# Sheet1.net
KiCad netlist of a schematic drawn in Altium Designer
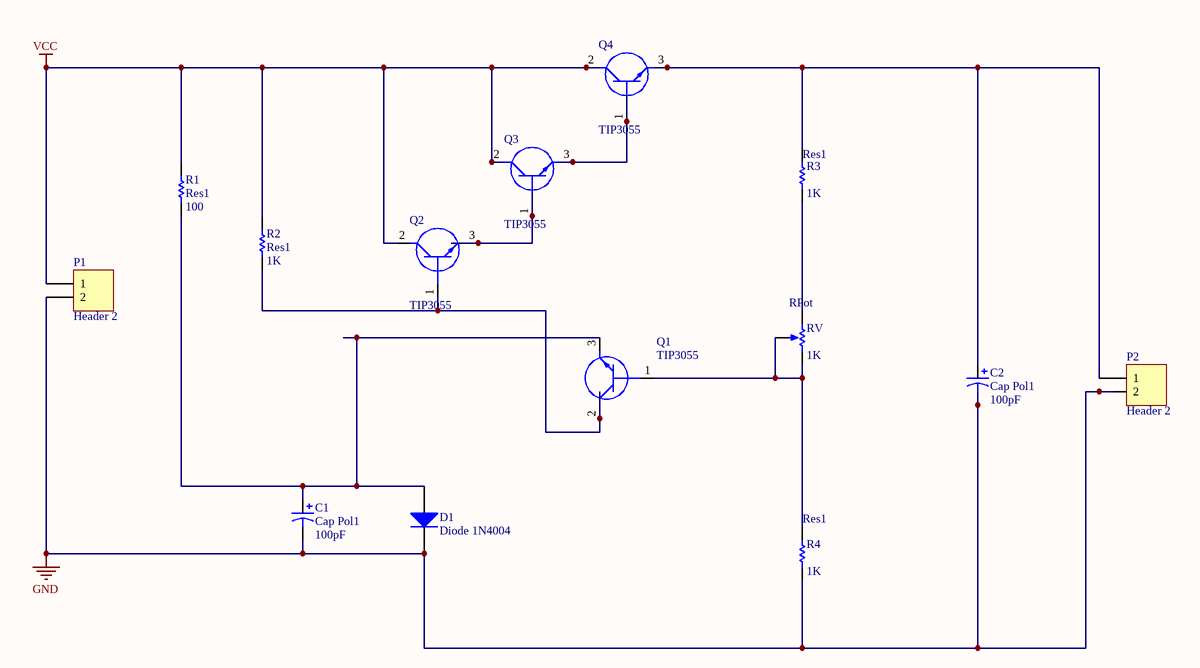
[diagram p0: Sheet1.SchDoc]

(export (version "E")
  (design (tool "Eeschema 10.0.6"))
  (components
    (comp (ref "C1")
      (value "Cap Pol1")
      (footprint "RB7.6-15")
      (description "Polarized Capacitor (Radial)")
      (fields (field (name "ALTIUM_VALUE") "100pF") (field (name "PUBLISHER") "Altium Limited"))
      (libsource (lib "Miscellaneous Devices") (part "Cap Pol1"))
    )
    (comp (ref "C2")
      (value "Cap Pol1")
      (footprint "RB7.6-15")
      (description "Polarized Capacitor (Radial)")
      (fields (field (name "ALTIUM_VALUE") "100pF") (field (name "PUBLISHER") "Altium Limited"))
      (libsource (lib "Miscellaneous Devices") (part "Cap Pol1"))
    )
    (comp (ref "D1")
      (value "Diode 1N4004")
      (footprint "DO-41")
      (description "1 Amp General Purpose Rectifier")
      (fields (field (name "PUBLISHER") "Altium Limited"))
      (libsource (lib "Miscellaneous Devices") (part "Diode 1N4004"))
    )
    (comp (ref "P1")
      (value "Header 2")
      (footprint "HDR1X2")
      (description "Header, 2-Pin")
      (fields (field (name "PUBLISHER") "Altium Limited"))
      (libsource (lib "Miscellaneous Connectors") (part "Header 2"))
    )
    (comp (ref "P2")
      (value "Header 2")
      (footprint "HDR1X2")
      (description "Header, 2-Pin")
      (fields (field (name "PUBLISHER") "Altium Limited"))
      (libsource (lib "Miscellaneous Connectors") (part "Header 2"))
    )
    (comp (ref "Q1")
      (value "TIP3055")
      (footprint "SamacSys:TO545P515X1560X2445-3P")
      (description "Transistor BJT NPN")
      (fields (field (name "MOUSER PART NUMBER") "511-TIP3055") (field (name "RS PART NUMBER") "1686168"))
      (libsource (lib "*") (part "TIP3055"))
    )
    (comp (ref "Q2")
      (value "TIP3055")
      (footprint "SamacSys:TO545P515X1560X2445-3P")
      (description "Transistor BJT NPN")
      (fields (field (name "MOUSER PART NUMBER") "511-TIP3055") (field (name "RS PART NUMBER") "1686168"))
      (libsource (lib "*") (part "TIP3055"))
    )
    (comp (ref "Q3")
      (value "TIP3055")
      (footprint "SamacSys:TO545P515X1560X2445-3P")
      (description "Transistor BJT NPN")
      (fields (field (name "MOUSER PART NUMBER") "511-TIP3055") (field (name "RS PART NUMBER") "1686168"))
      (libsource (lib "*") (part "TIP3055"))
    )
    (comp (ref "Q4")
      (value "TIP3055")
      (footprint "SamacSys:TO545P515X1560X2445-3P")
      (description "Transistor BJT NPN")
      (fields (field (name "MOUSER PART NUMBER") "511-TIP3055") (field (name "RS PART NUMBER") "1686168"))
      (libsource (lib "*") (part "TIP3055"))
    )
    (comp (ref "R1")
      (value "Res1")
      (footprint "AXIAL-0.3")
      (description "Resistor")
      (fields (field (name "ALTIUM_VALUE") "100") (field (name "PUBLISHER") "Altium Limited"))
      (libsource (lib "Miscellaneous Devices") (part "Res1"))
    )
    (comp (ref "R2")
      (value "Res1")
      (footprint "AXIAL-0.3")
      (description "Resistor")
      (fields (field (name "ALTIUM_VALUE") "1K") (field (name "PUBLISHER") "Altium Limited"))
      (libsource (lib "Miscellaneous Devices") (part "Res1"))
    )
    (comp (ref "R3")
      (value "Res1")
      (footprint "AXIAL-0.3")
      (description "Resistor")
      (fields (field (name "ALTIUM_VALUE") "1K") (field (name "PUBLISHER") "Altium Limited"))
      (libsource (lib "Miscellaneous Devices") (part "Res1"))
    )
    (comp (ref "R4")
      (value "Res1")
      (footprint "AXIAL-0.3")
      (description "Resistor")
      (fields (field (name "ALTIUM_VALUE") "1K") (field (name "PUBLISHER") "Altium Limited"))
      (libsource (lib "Miscellaneous Devices") (part "Res1"))
    )
    (comp (ref "RV")
      (value "RPot")
      (footprint "VR5")
      (description "Potentiometer")
      (fields (field (name "ALTIUM_VALUE") "1K") (field (name "PUBLISHER") "Altium Limited"))
      (libsource (lib "Miscellaneous Devices") (part "RPot"))
    )
  )
  (nets
    (net (code "1") (name "GND") (class "Default")
      (node (ref "C1") (pin "2") (pinfunction "2_2") (pintype "passive"))
      (node (ref "C2") (pin "2") (pinfunction "2_2") (pintype "passive"))
      (node (ref "D1") (pin "2") (pinfunction "K_2") (pintype "passive"))
      (node (ref "P1") (pin "2") (pinfunction "2_2") (pintype "passive"))
      (node (ref "P2") (pin "2") (pinfunction "2_2") (pintype "passive"))
      (node (ref "R4") (pin "1") (pinfunction "1_1") (pintype "passive"))
    )
    (net (code "2") (name "Net-(D1-A)") (class "Default")
      (node (ref "C1") (pin "1") (pinfunction "1_1") (pintype "passive"))
      (node (ref "D1") (pin "1") (pinfunction "A_1") (pintype "passive"))
      (node (ref "Q1") (pin "3") (pinfunction "E_3") (pintype "passive"))
      (node (ref "R1") (pin "1") (pinfunction "1_1") (pintype "passive"))
    )
    (net (code "3") (name "Net-(Q1-B)") (class "Default")
      (node (ref "Q1") (pin "1") (pinfunction "B_1") (pintype "passive"))
      (node (ref "R4") (pin "2") (pinfunction "2_2") (pintype "passive"))
      (node (ref "RV") (pin "2") (pinfunction "BOT_2") (pintype "passive"))
      (node (ref "RV") (pin "3") (pinfunction "TAP_3") (pintype "passive"))
    )
    (net (code "4") (name "Net-(Q1-C)") (class "Default")
      (node (ref "Q1") (pin "2") (pinfunction "C_2") (pintype "passive"))
      (node (ref "Q2") (pin "1") (pinfunction "B_1") (pintype "passive"))
      (node (ref "R2") (pin "1") (pinfunction "1_1") (pintype "passive"))
    )
    (net (code "5") (name "Net-(Q2-E)") (class "Default")
      (node (ref "Q2") (pin "3") (pinfunction "E_3") (pintype "passive"))
      (node (ref "Q3") (pin "1") (pinfunction "B_1") (pintype "passive"))
    )
    (net (code "6") (name "Net-(Q3-E)") (class "Default")
      (node (ref "Q3") (pin "3") (pinfunction "E_3") (pintype "passive"))
      (node (ref "Q4") (pin "1") (pinfunction "B_1") (pintype "passive"))
    )
    (net (code "7") (name "Net-(Q4-E)") (class "Default")
      (node (ref "C2") (pin "1") (pinfunction "1_1") (pintype "passive"))
      (node (ref "P2") (pin "1") (pinfunction "1_1") (pintype "passive"))
      (node (ref "Q4") (pin "3") (pinfunction "E_3") (pintype "passive"))
      (node (ref "R3") (pin "2") (pinfunction "2_2") (pintype "passive"))
    )
    (net (code "8") (name "Net-(RV-TOP)") (class "Default")
      (node (ref "R3") (pin "1") (pinfunction "1_1") (pintype "passive"))
      (node (ref "RV") (pin "1") (pinfunction "TOP_1") (pintype "passive"))
    )
    (net (code "9") (name "VCC") (class "Default")
      (node (ref "P1") (pin "1") (pinfunction "1_1") (pintype "passive"))
      (node (ref "Q2") (pin "2") (pinfunction "C_2") (pintype "passive"))
      (node (ref "Q3") (pin "2") (pinfunction "C_2") (pintype "passive"))
      (node (ref "Q4") (pin "2") (pinfunction "C_2") (pintype "passive"))
      (node (ref "R1") (pin "2") (pinfunction "2_2") (pintype "passive"))
      (node (ref "R2") (pin "2") (pinfunction "2_2") (pintype "passive"))
    )
  )
)
